# TypeC_USB2_0.net
KiCad netlist of a schematic drawn in Altium Designer
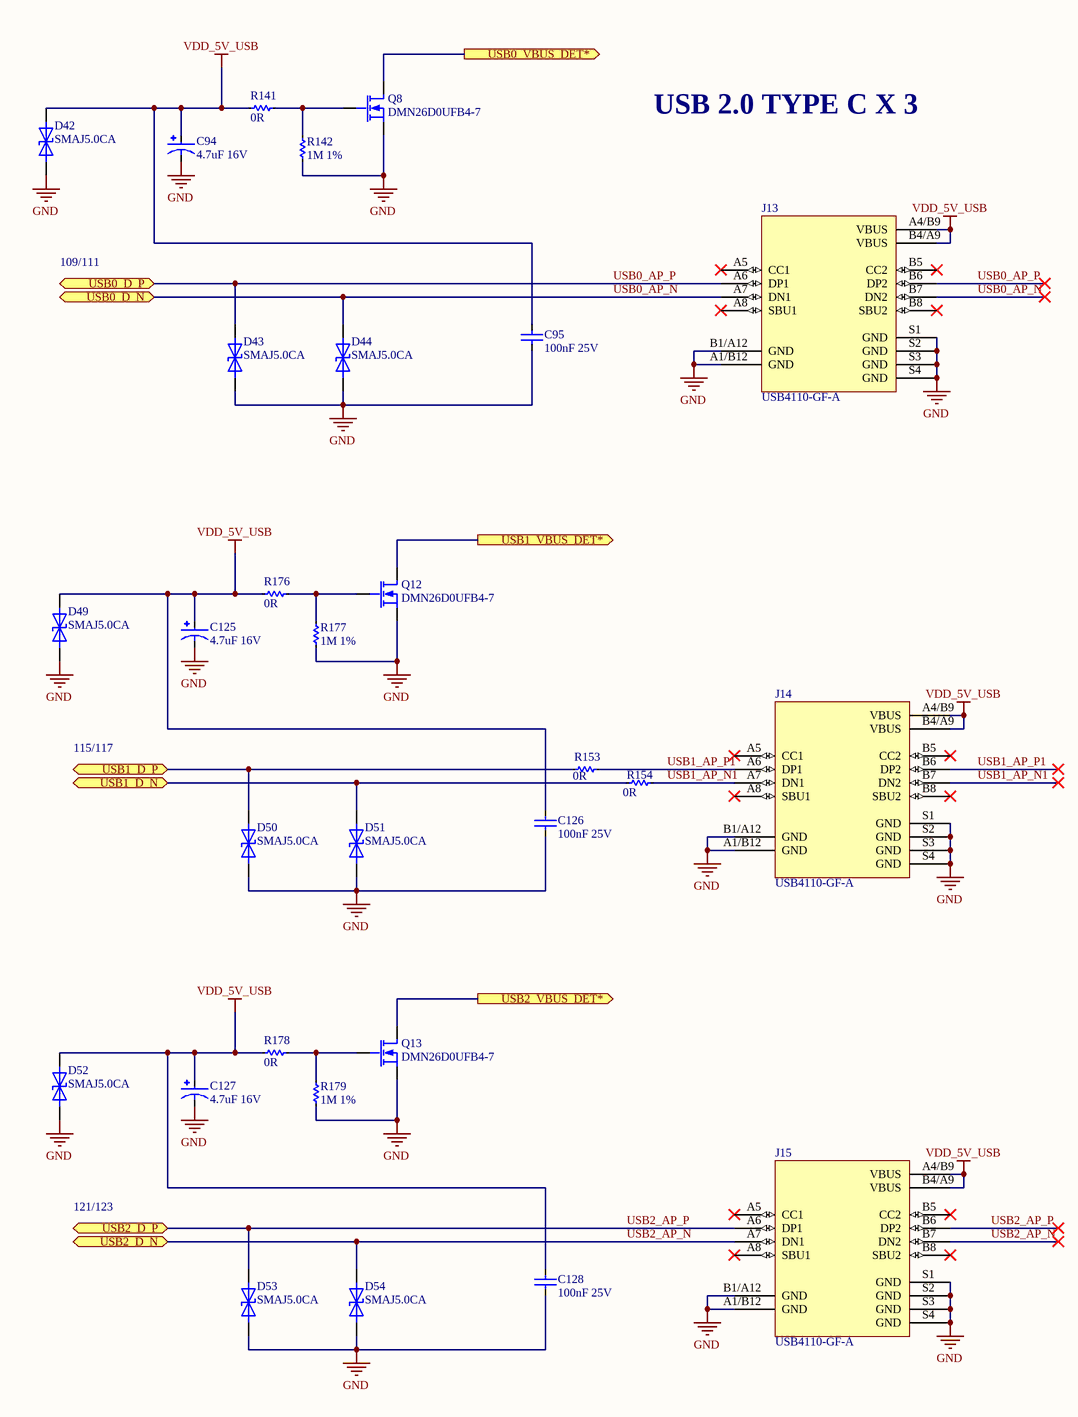
[diagram p0: TypeC_USB2.0.SchDoc]

(export (version "E")
  (design (tool "Eeschema 10.0.6"))
  (components
    (comp (ref "C94")
      (value "4.7uF 16V")
      (footprint "C1206_TANTALUM")
      (description "Cap Tant Solid 4.7uF 16V A CASE 10%( 3.2 X 1.6 X 1.6mm) Inward L SMD 3216-18 4 Ohm 125C T/R")
      (fields
        (field (name "MANUFACTURER") "Kyocera AVX")
        (field (name "MANUFACTURER PART NUMBER") "TAJA475K016RNJ")
      )
      (libsource (lib "GM_Altium_Library") (part "TAJA475K016RNJ"))
    )
    (comp (ref "C95")
      (value "100nF 25V")
      (footprint "C0402")
      (description "0402 100 nF 25 V ±10 % Tolerance X7R Surface Mount Multilayer Ceramic Capacitor")
      (fields
        (field (name "MANUFACTURER") "Kyocera AVX")
        (field (name "MANUFACTURER PART NUMBER") "04023C104KAT2A")
      )
      (libsource (lib "GM_Altium_Library") (part "04023C104KAT2A"))
    )
    (comp (ref "C125")
      (value "4.7uF 16V")
      (footprint "C1206_TANTALUM")
      (description "Cap Tant Solid 4.7uF 16V A CASE 10%( 3.2 X 1.6 X 1.6mm) Inward L SMD 3216-18 4 Ohm 125C T/R")
      (fields
        (field (name "MANUFACTURER") "Kyocera AVX")
        (field (name "MANUFACTURER PART NUMBER") "TAJA475K016RNJ")
      )
      (libsource (lib "GM_Altium_Library") (part "TAJA475K016RNJ"))
    )
    (comp (ref "C126")
      (value "100nF 25V")
      (footprint "C0402")
      (description "0402 100 nF 25 V ±10 % Tolerance X7R Surface Mount Multilayer Ceramic Capacitor")
      (fields
        (field (name "MANUFACTURER") "Kyocera AVX")
        (field (name "MANUFACTURER PART NUMBER") "04023C104KAT2A")
      )
      (libsource (lib "GM_Altium_Library") (part "04023C104KAT2A"))
    )
    (comp (ref "C127")
      (value "4.7uF 16V")
      (footprint "C1206_TANTALUM")
      (description "Cap Tant Solid 4.7uF 16V A CASE 10%( 3.2 X 1.6 X 1.6mm) Inward L SMD 3216-18 4 Ohm 125C T/R")
      (fields
        (field (name "MANUFACTURER") "Kyocera AVX")
        (field (name "MANUFACTURER PART NUMBER") "TAJA475K016RNJ")
      )
      (libsource (lib "GM_Altium_Library") (part "TAJA475K016RNJ"))
    )
    (comp (ref "C128")
      (value "100nF 25V")
      (footprint "C0402")
      (description "0402 100 nF 25 V ±10 % Tolerance X7R Surface Mount Multilayer Ceramic Capacitor")
      (fields
        (field (name "MANUFACTURER") "Kyocera AVX")
        (field (name "MANUFACTURER PART NUMBER") "04023C104KAT2A")
      )
      (libsource (lib "GM_Altium_Library") (part "04023C104KAT2A"))
    )
    (comp (ref "D42")
      (value "SMAJ5.0CA")
      (footprint "DO-214AC")
      (fields (field (name "MANUFACTURER") "Littelfuse"))
      (libsource (lib "GM_Altium_Library") (part "SMAJ5.0CA"))
    )
    (comp (ref "D43")
      (value "SMAJ5.0CA")
      (footprint "DO-214AC")
      (fields (field (name "MANUFACTURER") "Littelfuse"))
      (libsource (lib "GM_Altium_Library") (part "SMAJ5.0CA"))
    )
    (comp (ref "D44")
      (value "SMAJ5.0CA")
      (footprint "DO-214AC")
      (fields (field (name "MANUFACTURER") "Littelfuse"))
      (libsource (lib "GM_Altium_Library") (part "SMAJ5.0CA"))
    )
    (comp (ref "D49")
      (value "SMAJ5.0CA")
      (footprint "DO-214AC")
      (fields (field (name "MANUFACTURER") "Littelfuse"))
      (libsource (lib "GM_Altium_Library") (part "SMAJ5.0CA"))
    )
    (comp (ref "D50")
      (value "SMAJ5.0CA")
      (footprint "DO-214AC")
      (fields (field (name "MANUFACTURER") "Littelfuse"))
      (libsource (lib "GM_Altium_Library") (part "SMAJ5.0CA"))
    )
    (comp (ref "D51")
      (value "SMAJ5.0CA")
      (footprint "DO-214AC")
      (fields (field (name "MANUFACTURER") "Littelfuse"))
      (libsource (lib "GM_Altium_Library") (part "SMAJ5.0CA"))
    )
    (comp (ref "D52")
      (value "SMAJ5.0CA")
      (footprint "DO-214AC")
      (fields (field (name "MANUFACTURER") "Littelfuse"))
      (libsource (lib "GM_Altium_Library") (part "SMAJ5.0CA"))
    )
    (comp (ref "D53")
      (value "SMAJ5.0CA")
      (footprint "DO-214AC")
      (fields (field (name "MANUFACTURER") "Littelfuse"))
      (libsource (lib "GM_Altium_Library") (part "SMAJ5.0CA"))
    )
    (comp (ref "D54")
      (value "SMAJ5.0CA")
      (footprint "DO-214AC")
      (fields (field (name "MANUFACTURER") "Littelfuse"))
      (libsource (lib "GM_Altium_Library") (part "SMAJ5.0CA"))
    )
    (comp (ref "J13")
      (value "USB4110-GF-A")
      (footprint "USB4110-GF-A")
      (description "Conn USB 2.0 Type C RCP 16 POS 0.3mm/0.5mm Solder ST SMD 16 Terminal 1 Port T/R")
      (fields (field (name "MANUFACTURER") "Global Connector Technology"))
      (libsource (lib "GM_Altium_Library") (part "USB4110-GF-A"))
    )
    (comp (ref "J14")
      (value "USB4110-GF-A")
      (footprint "USB4110-GF-A")
      (description "Conn USB 2.0 Type C RCP 16 POS 0.3mm/0.5mm Solder ST SMD 16 Terminal 1 Port T/R")
      (fields (field (name "MANUFACTURER") "Global Connector Technology"))
      (libsource (lib "GM_Altium_Library") (part "USB4110-GF-A"))
    )
    (comp (ref "J15")
      (value "USB4110-GF-A")
      (footprint "USB4110-GF-A")
      (description "Conn USB 2.0 Type C RCP 16 POS 0.3mm/0.5mm Solder ST SMD 16 Terminal 1 Port T/R")
      (fields (field (name "MANUFACTURER") "Global Connector Technology"))
      (libsource (lib "GM_Altium_Library") (part "USB4110-GF-A"))
    )
    (comp (ref "Q8")
      (value "DMN26D0UFB4-7")
      (footprint "DFN1006-3")
      (description "Single N-Channel 20 V 350 mW Silicon Surface Mount Mosfet - DFN-3")
      (fields (field (name "MANUFACTURER") "Diodes"))
      (libsource (lib "GM_Altium_Library") (part "DMN26D0UFB4-7"))
    )
    (comp (ref "Q12")
      (value "DMN26D0UFB4-7")
      (footprint "DFN1006-3")
      (description "Single N-Channel 20 V 350 mW Silicon Surface Mount Mosfet - DFN-3")
      (fields (field (name "MANUFACTURER") "Diodes"))
      (libsource (lib "GM_Altium_Library") (part "DMN26D0UFB4-7"))
    )
    (comp (ref "Q13")
      (value "DMN26D0UFB4-7")
      (footprint "DFN1006-3")
      (description "Single N-Channel 20 V 350 mW Silicon Surface Mount Mosfet - DFN-3")
      (fields (field (name "MANUFACTURER") "Diodes"))
      (libsource (lib "GM_Altium_Library") (part "DMN26D0UFB4-7"))
    )
    (comp (ref "R141")
      (value "0R")
      (footprint "R0603")
      (description "RES SMD 0 OHM JUMPER 1/10W 0603")
      (fields
        (field (name "MANUFACTURER") "Bourns")
        (field (name "MANUFACTURER PART NUMBER") "CR0603-J/-000ELF")
      )
      (libsource (lib "GM_Altium_Library") (part "CR0603-J/-000ELF"))
    )
    (comp (ref "R142")
      (value "1M 1%")
      (footprint "R0402")
      (description "RES SMD 1M OHM 1% 1/16W 0402")
      (fields
        (field (name "MANUFACTURER") "Yageo")
        (field (name "MANUFACTURER PART NUMBER") "AC0402FR-071ML")
      )
      (libsource (lib "GM_Altium_Library") (part "AC0402FR-071ML"))
    )
    (comp (ref "R153")
      (value "0R")
      (footprint "R0402")
      (description "Res Jumper Thick Film 0402 0 Ohm 5% 1/16W Molded SMD Paper T/R")
      (fields
        (field (name "MANUFACTURER") "Yageo")
        (field (name "MANUFACTURER PART NUMBER") "RC0402JR-070RP")
      )
      (libsource (lib "GM_Altium_Library") (part "RC0402JR-070RP"))
    )
    (comp (ref "R154")
      (value "0R")
      (footprint "R0402")
      (description "Res Jumper Thick Film 0402 0 Ohm 5% 1/16W Molded SMD Paper T/R")
      (fields
        (field (name "MANUFACTURER") "Yageo")
        (field (name "MANUFACTURER PART NUMBER") "RC0402JR-070RP")
      )
      (libsource (lib "GM_Altium_Library") (part "RC0402JR-070RP"))
    )
    (comp (ref "R176")
      (value "0R")
      (footprint "R0603")
      (description "RES SMD 0 OHM JUMPER 1/10W 0603")
      (fields
        (field (name "MANUFACTURER") "Bourns")
        (field (name "MANUFACTURER PART NUMBER") "CR0603-J/-000ELF")
      )
      (libsource (lib "GM_Altium_Library") (part "CR0603-J/-000ELF"))
    )
    (comp (ref "R177")
      (value "1M 1%")
      (footprint "R0402")
      (description "RES SMD 1M OHM 1% 1/16W 0402")
      (fields
        (field (name "MANUFACTURER") "Yageo")
        (field (name "MANUFACTURER PART NUMBER") "AC0402FR-071ML")
      )
      (libsource (lib "GM_Altium_Library") (part "AC0402FR-071ML"))
    )
    (comp (ref "R178")
      (value "0R")
      (footprint "R0603")
      (description "RES SMD 0 OHM JUMPER 1/10W 0603")
      (fields
        (field (name "MANUFACTURER") "Bourns")
        (field (name "MANUFACTURER PART NUMBER") "CR0603-J/-000ELF")
      )
      (libsource (lib "GM_Altium_Library") (part "CR0603-J/-000ELF"))
    )
    (comp (ref "R179")
      (value "1M 1%")
      (footprint "R0402")
      (description "RES SMD 1M OHM 1% 1/16W 0402")
      (fields
        (field (name "MANUFACTURER") "Yageo")
        (field (name "MANUFACTURER PART NUMBER") "AC0402FR-071ML")
      )
      (libsource (lib "GM_Altium_Library") (part "AC0402FR-071ML"))
    )
  )
  (nets
    (net (code "1") (name "/USB0_AP_N") (class "Default")
      (node (ref "D44") (pin "A") (pinfunction "A_A") (pintype "passive"))
      (node (ref "J13") (pin "A7") (pinfunction "DN1_A7") (pintype "bidirectional"))
      (node (ref "J13") (pin "B7") (pinfunction "DN2_B7") (pintype "bidirectional"))
    )
    (net (code "2") (name "/USB0_AP_P") (class "Default")
      (node (ref "D43") (pin "A") (pinfunction "A_A") (pintype "passive"))
      (node (ref "J13") (pin "A6") (pinfunction "DP1_A6") (pintype "bidirectional"))
      (node (ref "J13") (pin "B6") (pinfunction "DP2_B6") (pintype "bidirectional"))
    )
    (net (code "3") (name "/USB0_VBUS_DET*") (class "Default")
      (node (ref "Q8") (pin "3") (pinfunction "D_3") (pintype "passive"))
    )
    (net (code "4") (name "/USB1_AP_N1") (class "Default")
      (node (ref "J14") (pin "A7") (pinfunction "DN1_A7") (pintype "bidirectional"))
      (node (ref "J14") (pin "B7") (pinfunction "DN2_B7") (pintype "bidirectional"))
      (node (ref "R154") (pin "2") (pinfunction "2_2") (pintype "passive"))
    )
    (net (code "5") (name "/USB1_AP_P1") (class "Default")
      (node (ref "J14") (pin "A6") (pinfunction "DP1_A6") (pintype "bidirectional"))
      (node (ref "J14") (pin "B6") (pinfunction "DP2_B6") (pintype "bidirectional"))
      (node (ref "R153") (pin "2") (pinfunction "2_2") (pintype "passive"))
    )
    (net (code "6") (name "/USB1_D_N") (class "Default")
      (node (ref "D51") (pin "A") (pinfunction "A_A") (pintype "passive"))
      (node (ref "R154") (pin "1") (pinfunction "1_1") (pintype "passive"))
    )
    (net (code "7") (name "/USB1_D_P") (class "Default")
      (node (ref "D50") (pin "A") (pinfunction "A_A") (pintype "passive"))
      (node (ref "R153") (pin "1") (pinfunction "1_1") (pintype "passive"))
    )
    (net (code "8") (name "/USB1_VBUS_DET*") (class "Default")
      (node (ref "Q12") (pin "3") (pinfunction "D_3") (pintype "passive"))
    )
    (net (code "9") (name "/USB2_AP_N") (class "Default")
      (node (ref "D54") (pin "A") (pinfunction "A_A") (pintype "passive"))
      (node (ref "J15") (pin "A7") (pinfunction "DN1_A7") (pintype "bidirectional"))
      (node (ref "J15") (pin "B7") (pinfunction "DN2_B7") (pintype "bidirectional"))
    )
    (net (code "10") (name "/USB2_AP_P") (class "Default")
      (node (ref "D53") (pin "A") (pinfunction "A_A") (pintype "passive"))
      (node (ref "J15") (pin "A6") (pinfunction "DP1_A6") (pintype "bidirectional"))
      (node (ref "J15") (pin "B6") (pinfunction "DP2_B6") (pintype "bidirectional"))
    )
    (net (code "11") (name "/USB2_VBUS_DET*") (class "Default")
      (node (ref "Q13") (pin "3") (pinfunction "D_3") (pintype "passive"))
    )
    (net (code "12") (name "GND") (class "Default")
      (node (ref "C125") (pin "2") (pinfunction "-_2") (pintype "passive"))
      (node (ref "C126") (pin "1") (pinfunction "1_1") (pintype "passive"))
      (node (ref "C127") (pin "2") (pinfunction "-_2") (pintype "passive"))
      (node (ref "C128") (pin "1") (pinfunction "1_1") (pintype "passive"))
      (node (ref "C94") (pin "2") (pinfunction "-_2") (pintype "passive"))
      (node (ref "C95") (pin "1") (pinfunction "1_1") (pintype "passive"))
      (node (ref "D42") (pin "C") (pinfunction "C_C") (pintype "passive"))
      (node (ref "D43") (pin "C") (pinfunction "C_C") (pintype "passive"))
      (node (ref "D44") (pin "C") (pinfunction "C_C") (pintype "passive"))
      (node (ref "D49") (pin "C") (pinfunction "C_C") (pintype "passive"))
      (node (ref "D50") (pin "C") (pinfunction "C_C") (pintype "passive"))
      (node (ref "D51") (pin "C") (pinfunction "C_C") (pintype "passive"))
      (node (ref "D52") (pin "C") (pinfunction "C_C") (pintype "passive"))
      (node (ref "D53") (pin "C") (pinfunction "C_C") (pintype "passive"))
      (node (ref "D54") (pin "C") (pinfunction "C_C") (pintype "passive"))
      (node (ref "J13") (pin "A1/B12") (pinfunction "GND_A1/B12") (pintype "power_in"))
      (node (ref "J13") (pin "B1/A12") (pinfunction "GND_B1/A12") (pintype "power_in"))
      (node (ref "J13") (pin "S1") (pinfunction "GND_S1") (pintype "power_in"))
      (node (ref "J13") (pin "S2") (pinfunction "GND_S2") (pintype "power_in"))
      (node (ref "J13") (pin "S3") (pinfunction "GND_S3") (pintype "power_in"))
      (node (ref "J13") (pin "S4") (pinfunction "GND_S4") (pintype "power_in"))
      (node (ref "J14") (pin "A1/B12") (pinfunction "GND_A1/B12") (pintype "power_in"))
      (node (ref "J14") (pin "B1/A12") (pinfunction "GND_B1/A12") (pintype "power_in"))
      (node (ref "J14") (pin "S1") (pinfunction "GND_S1") (pintype "power_in"))
      (node (ref "J14") (pin "S2") (pinfunction "GND_S2") (pintype "power_in"))
      (node (ref "J14") (pin "S3") (pinfunction "GND_S3") (pintype "power_in"))
      (node (ref "J14") (pin "S4") (pinfunction "GND_S4") (pintype "power_in"))
      (node (ref "J15") (pin "A1/B12") (pinfunction "GND_A1/B12") (pintype "power_in"))
      (node (ref "J15") (pin "B1/A12") (pinfunction "GND_B1/A12") (pintype "power_in"))
      (node (ref "J15") (pin "S1") (pinfunction "GND_S1") (pintype "power_in"))
      (node (ref "J15") (pin "S2") (pinfunction "GND_S2") (pintype "power_in"))
      (node (ref "J15") (pin "S3") (pinfunction "GND_S3") (pintype "power_in"))
      (node (ref "J15") (pin "S4") (pinfunction "GND_S4") (pintype "power_in"))
      (node (ref "Q12") (pin "2") (pinfunction "S_2") (pintype "passive"))
      (node (ref "Q13") (pin "2") (pinfunction "S_2") (pintype "passive"))
      (node (ref "Q8") (pin "2") (pinfunction "S_2") (pintype "passive"))
      (node (ref "R142") (pin "1") (pinfunction "1_1") (pintype "passive"))
      (node (ref "R177") (pin "1") (pinfunction "1_1") (pintype "passive"))
      (node (ref "R179") (pin "1") (pinfunction "1_1") (pintype "passive"))
    )
    (net (code "13") (name "Net-(Q8-G)") (class "Default")
      (node (ref "Q8") (pin "1") (pinfunction "G_1") (pintype "passive"))
      (node (ref "R141") (pin "2") (pinfunction "2_2") (pintype "passive"))
      (node (ref "R142") (pin "2") (pinfunction "2_2") (pintype "passive"))
    )
    (net (code "14") (name "Net-(Q12-G)") (class "Default")
      (node (ref "Q12") (pin "1") (pinfunction "G_1") (pintype "passive"))
      (node (ref "R176") (pin "2") (pinfunction "2_2") (pintype "passive"))
      (node (ref "R177") (pin "2") (pinfunction "2_2") (pintype "passive"))
    )
    (net (code "15") (name "Net-(Q13-G)") (class "Default")
      (node (ref "Q13") (pin "1") (pinfunction "G_1") (pintype "passive"))
      (node (ref "R178") (pin "2") (pinfunction "2_2") (pintype "passive"))
      (node (ref "R179") (pin "2") (pinfunction "2_2") (pintype "passive"))
    )
    (net (code "16") (name "VDD_5V_USB") (class "Default")
      (node (ref "C125") (pin "1") (pinfunction "+1_1") (pintype "passive"))
      (node (ref "C126") (pin "2") (pinfunction "2_2") (pintype "passive"))
      (node (ref "C127") (pin "1") (pinfunction "+1_1") (pintype "passive"))
      (node (ref "C128") (pin "2") (pinfunction "2_2") (pintype "passive"))
      (node (ref "C94") (pin "1") (pinfunction "+1_1") (pintype "passive"))
      (node (ref "C95") (pin "2") (pinfunction "2_2") (pintype "passive"))
      (node (ref "D42") (pin "A") (pinfunction "A_A") (pintype "passive"))
      (node (ref "D49") (pin "A") (pinfunction "A_A") (pintype "passive"))
      (node (ref "D52") (pin "A") (pinfunction "A_A") (pintype "passive"))
      (node (ref "J13") (pin "A4/B9") (pinfunction "VBUS_A4/B9") (pintype "power_in"))
      (node (ref "J13") (pin "B4/A9") (pinfunction "VBUS_B4/A9") (pintype "power_in"))
      (node (ref "J14") (pin "A4/B9") (pinfunction "VBUS_A4/B9") (pintype "power_in"))
      (node (ref "J14") (pin "B4/A9") (pinfunction "VBUS_B4/A9") (pintype "power_in"))
      (node (ref "J15") (pin "A4/B9") (pinfunction "VBUS_A4/B9") (pintype "power_in"))
      (node (ref "J15") (pin "B4/A9") (pinfunction "VBUS_B4/A9") (pintype "power_in"))
      (node (ref "R141") (pin "1") (pinfunction "1_1") (pintype "passive"))
      (node (ref "R176") (pin "1") (pinfunction "1_1") (pintype "passive"))
      (node (ref "R178") (pin "1") (pinfunction "1_1") (pintype "passive"))
    )
    (net (code "17") (name "unconnected-(J13-CC1-PadA5)") (class "Default")
      (node (ref "J13") (pin "A5") (pinfunction "CC1_A5") (pintype "bidirectional+no_connect"))
    )
    (net (code "18") (name "unconnected-(J13-CC2-PadB5)") (class "Default")
      (node (ref "J13") (pin "B5") (pinfunction "CC2_B5") (pintype "bidirectional+no_connect"))
    )
    (net (code "19") (name "unconnected-(J13-SBU1-PadA8)") (class "Default")
      (node (ref "J13") (pin "A8") (pinfunction "SBU1_A8") (pintype "bidirectional+no_connect"))
    )
    (net (code "20") (name "unconnected-(J13-SBU2-PadB8)") (class "Default")
      (node (ref "J13") (pin "B8") (pinfunction "SBU2_B8") (pintype "bidirectional+no_connect"))
    )
    (net (code "21") (name "unconnected-(J14-CC1-PadA5)") (class "Default")
      (node (ref "J14") (pin "A5") (pinfunction "CC1_A5") (pintype "bidirectional+no_connect"))
    )
    (net (code "22") (name "unconnected-(J14-CC2-PadB5)") (class "Default")
      (node (ref "J14") (pin "B5") (pinfunction "CC2_B5") (pintype "bidirectional+no_connect"))
    )
    (net (code "23") (name "unconnected-(J14-SBU1-PadA8)") (class "Default")
      (node (ref "J14") (pin "A8") (pinfunction "SBU1_A8") (pintype "bidirectional+no_connect"))
    )
    (net (code "24") (name "unconnected-(J14-SBU2-PadB8)") (class "Default")
      (node (ref "J14") (pin "B8") (pinfunction "SBU2_B8") (pintype "bidirectional+no_connect"))
    )
    (net (code "25") (name "unconnected-(J15-CC1-PadA5)") (class "Default")
      (node (ref "J15") (pin "A5") (pinfunction "CC1_A5") (pintype "bidirectional+no_connect"))
    )
    (net (code "26") (name "unconnected-(J15-CC2-PadB5)") (class "Default")
      (node (ref "J15") (pin "B5") (pinfunction "CC2_B5") (pintype "bidirectional+no_connect"))
    )
    (net (code "27") (name "unconnected-(J15-SBU1-PadA8)") (class "Default")
      (node (ref "J15") (pin "A8") (pinfunction "SBU1_A8") (pintype "bidirectional+no_connect"))
    )
    (net (code "28") (name "unconnected-(J15-SBU2-PadB8)") (class "Default")
      (node (ref "J15") (pin "B8") (pinfunction "SBU2_B8") (pintype "bidirectional+no_connect"))
    )
  )
)
